# Sheet1.net
KiCad netlist of a schematic drawn in Altium Designer
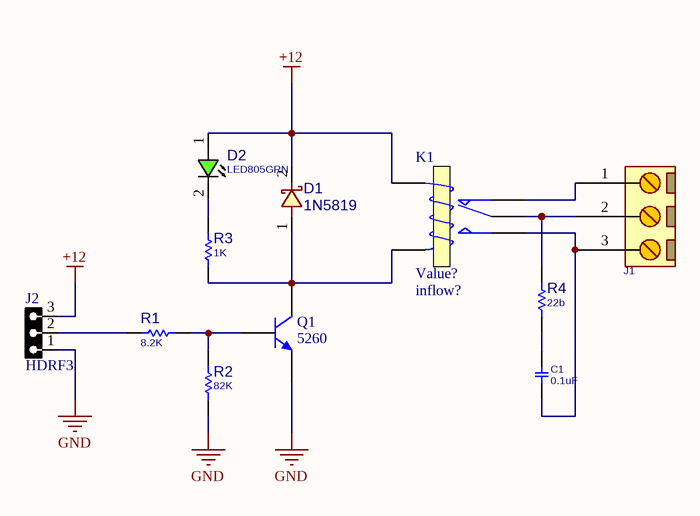
[diagram p0: Sheet1.SchDoc]

(export (version "E")
  (design (tool "Eeschema 10.0.6"))
  (components
    (comp (ref "C1")
      (value "0.1uF")
      (footprint "C_PLY_13X5")
      (description "CAP, FILM, 10nF, 630V")
      (fields (field (name "MANF_P#") "MANF_PART#") (field (name "MANF") "MANF"))
      (libsource (lib "Chila_PCB") (part "CAP_THD_FILMPLY_10N630V"))
    )
    (comp (ref "D1")
      (value "1N5819")
      (footprint "D_SOD123W")
      (description "DIODE, SCHOTTKY, 40V, 1A")
      (fields (field (name "MANF") "DIODES") (field (name "MANF_P#") "1N5819HW-7-F"))
      (libsource (lib "Chila_PCB") (part "DIODE_SMD_SCHOTTKY_1N5819"))
    )
    (comp (ref "D2")
      (value "LED805GRN")
      (footprint "LED0805GRN")
      (description "LED, SMD, 0805, GREEN")
      (libsource (lib "Chila_PCB") (part "LED_SMD_0805_GRN"))
    )
    (comp (ref "J1")
      (value "CONN_GMSTB3")
      (footprint "GMSTB762_3")
      (description "CONN, PHOENIX MSTB, 5-G, 5.08mm pitch")
      (fields (field (name "MANF_P#") "GMSTB 2,5/3-G-7,62"))
      (libsource (lib "Chila_PCB") (part "CONN_GMSTB762_3"))
    )
    (comp (ref "J2")
      (value "HDRF3")
      (footprint "HDR_F_1X3")
      (description "CONN, HEADER, Female, pitch: 2.54mm, 3POS")
      (libsource (lib "Chila_PCB") (part "HDR_F_1X3"))
    )
    (comp (ref "K1")
      (value "Value?")
      (footprint "Relay 18.85x15.35x15.70")
      (description "SPDT Relay")
      (fields (field (name "INFLOW") "inflow?"))
      (libsource (lib "aKaReZa") (part "SW_Relay_SPDT"))
    )
    (comp (ref "Q1")
      (value "NPN")
      (footprint "SOT23_N")
      (description "NPN Switching Transistors")
      (fields (field (name "INFLOW") "5260"))
      (libsource (lib "aKaReZa") (part "Semi_BJT_2N2222_SMD"))
    )
    (comp (ref "R1")
      (value "8.2K")
      (footprint "R0805")
      (description "RESISTOR, SMD")
      (libsource (lib "Chila_PCB") (part "RES_SMD_0805"))
    )
    (comp (ref "R2")
      (value "82K")
      (footprint "R0805")
      (description "RESISTOR, SMD")
      (libsource (lib "Chila_PCB") (part "RES_SMD_0805"))
    )
    (comp (ref "R3")
      (value "1K")
      (footprint "R0805")
      (description "RESISTOR, SMD")
      (libsource (lib "Chila_PCB") (part "RES_SMD_0805"))
    )
    (comp (ref "R4")
      (value "22b")
      (footprint "R3W_AX09")
      (description "RESISTOR, THD")
      (fields (field (name "MANF_P#") "RK73H1ETTP4701F") (field (name "MANF") "KOA SPEER"))
      (libsource (lib "Chila_PCB") (part "RES_THD"))
    )
  )
  (nets
    (net (code "1") (name "+12") (class "Default")
      (node (ref "D1") (pin "2") (pinfunction "2_2") (pintype "passive"))
      (node (ref "D2") (pin "1") (pinfunction "ANODE_1") (pintype "passive"))
      (node (ref "J2") (pin "3") (pinfunction "3_3") (pintype "passive"))
      (node (ref "K1") (pin "4") (pinfunction "T1_4") (pintype "passive"))
    )
    (net (code "2") (name "GND") (class "Default")
      (node (ref "J2") (pin "1") (pinfunction "1_1") (pintype "passive"))
      (node (ref "Q1") (pin "2") (pinfunction "E_2") (pintype "passive"))
      (node (ref "R2") (pin "1") (pinfunction "1_1") (pintype "passive"))
    )
    (net (code "3") (name "Net-(C1-Pad2)") (class "Default")
      (node (ref "C1") (pin "2") (pinfunction "2_2") (pintype "passive"))
      (node (ref "R4") (pin "1") (pinfunction "1_1") (pintype "passive"))
    )
    (net (code "4") (name "Net-(D2-CATHODE)") (class "Default")
      (node (ref "D2") (pin "2") (pinfunction "CATHODE_2") (pintype "passive"))
      (node (ref "R3") (pin "2") (pinfunction "2_2") (pintype "passive"))
    )
    (net (code "5") (name "Net-(J2-Pad2)") (class "Default")
      (node (ref "J2") (pin "2") (pinfunction "2_2") (pintype "passive"))
      (node (ref "R1") (pin "1") (pinfunction "1_1") (pintype "passive"))
    )
    (net (code "6") (name "Net-(K1-COM)") (class "Default")
      (node (ref "J1") (pin "2") (pinfunction "2_2") (pintype "passive"))
      (node (ref "K1") (pin "1") (pinfunction "COM_1") (pintype "passive"))
      (node (ref "R4") (pin "2") (pinfunction "2_2") (pintype "passive"))
    )
    (net (code "7") (name "Net-(K1-NC)") (class "Default")
      (node (ref "J1") (pin "1") (pinfunction "1_1") (pintype "passive"))
      (node (ref "K1") (pin "2") (pinfunction "NC_2") (pintype "passive"))
    )
    (net (code "8") (name "Net-(K1-NO)") (class "Default")
      (node (ref "C1") (pin "1") (pinfunction "1_1") (pintype "passive"))
      (node (ref "J1") (pin "3") (pinfunction "3_3") (pintype "passive"))
      (node (ref "K1") (pin "3") (pinfunction "NO_3") (pintype "passive"))
    )
    (net (code "9") (name "Net-(K1-T2)") (class "Default")
      (node (ref "D1") (pin "1") (pinfunction "1_1") (pintype "passive"))
      (node (ref "K1") (pin "5") (pinfunction "T2_5") (pintype "passive"))
      (node (ref "Q1") (pin "3") (pinfunction "C_3") (pintype "passive"))
      (node (ref "R3") (pin "1") (pinfunction "1_1") (pintype "passive"))
    )
    (net (code "10") (name "Net-(Q1-B)") (class "Default")
      (node (ref "Q1") (pin "1") (pinfunction "B_1") (pintype "passive"))
      (node (ref "R1") (pin "2") (pinfunction "2_2") (pintype "passive"))
      (node (ref "R2") (pin "2") (pinfunction "2_2") (pintype "passive"))
    )
  )
)
